# stm32_tracker34.net
KiCad netlist of a schematic drawn in EAGLE
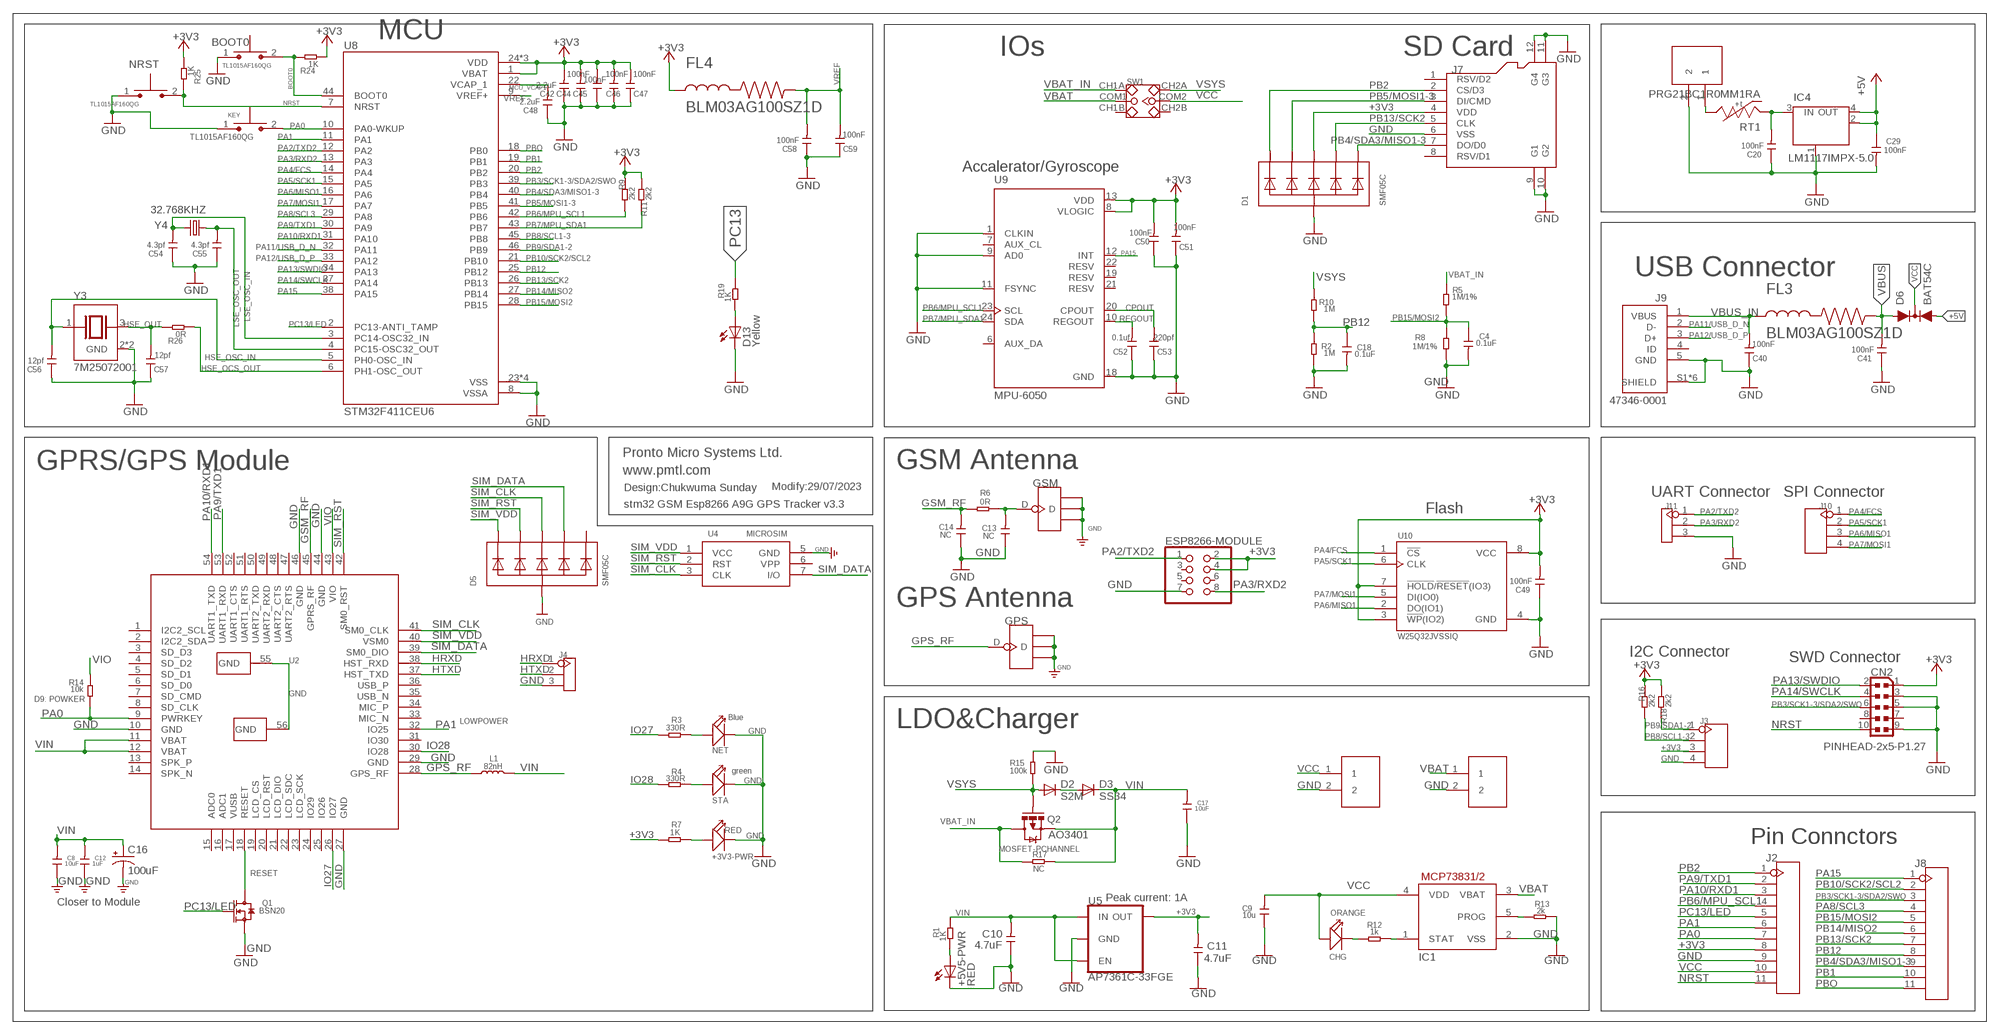
[diagram p0: schematic, sheet 1]

(export (version "E")
  (design (tool "Eeschema 10.0.6"))
  (components
    (comp (ref "+3V3-PWR")
      (value "RED")
      (footprint "eagle-import:LED-0603")
      (libsource (lib "eagle-import") (part "LED'0603'"))
    )
    (comp (ref "+5V5-PWR")
      (value "RED")
      (footprint "eagle-import:OPTO_CHIPLED_0805")
      (fields (field (name "PART_NUMBER") "KPT-2012SGC"))
      (libsource (lib "eagle-import") (part "OPTO_0043_KPT-2012SGC"))
    )
    (comp (ref "BOOT0")
      (value "TL1015AF160QG")
      (footprint "eagle-import:SW_TL1015AF160QG")
      (fields (field (name "MF") "E-Switch"))
      (libsource (lib "eagle-import") (part "TL1015AF160QG"))
    )
    (comp (ref "C4")
      (value "0.1uF")
      (footprint "eagle-import:C0603")
      (libsource (lib "eagle-import") (part "C-0603"))
    )
    (comp (ref "C8")
      (value "10uF")
      (footprint "eagle-import:C0603")
      (libsource (lib "eagle-import") (part "C-0603"))
    )
    (comp (ref "C9")
      (value "10u")
      (footprint "eagle-import:C0603")
      (libsource (lib "eagle-import") (part "C-0603"))
    )
    (comp (ref "C10")
      (value "4.7uF")
      (footprint "eagle-import:C0603")
      (libsource (lib "eagle-import") (part "C-0603"))
    )
    (comp (ref "C11")
      (value "4.7uF")
      (footprint "eagle-import:C0603")
      (libsource (lib "eagle-import") (part "C-0603"))
    )
    (comp (ref "C12")
      (value "1uF")
      (footprint "eagle-import:C0603")
      (libsource (lib "eagle-import") (part "C-0603"))
    )
    (comp (ref "C13")
      (value "NC")
      (footprint "eagle-import:C0402")
      (libsource (lib "eagle-import") (part "C-0402"))
    )
    (comp (ref "C14")
      (value "NC")
      (footprint "eagle-import:C0402")
      (libsource (lib "eagle-import") (part "C-0402"))
    )
    (comp (ref "C16")
      (value "100uF")
      (footprint "eagle-import:EIA3528")
      (libsource (lib "eagle-import") (part "68UF-POLAR-EIA3528-10V-10%(TANT)"))
    )
    (comp (ref "C17")
      (value "10uF")
      (footprint "eagle-import:C0603")
      (libsource (lib "eagle-import") (part "C-0603"))
    )
    (comp (ref "C18")
      (value "0.1uF")
      (footprint "eagle-import:C0603")
      (libsource (lib "eagle-import") (part "C-0603"))
    )
    (comp (ref "C20")
      (value "100nF")
      (footprint "eagle-import:C0603")
      (libsource (lib "eagle-import") (part "C-0603"))
    )
    (comp (ref "C29")
      (value "100nF")
      (footprint "eagle-import:C0603")
      (libsource (lib "eagle-import") (part "C-0603"))
    )
    (comp (ref "C40")
      (value "100nF")
      (footprint "eagle-import:C0603")
      (libsource (lib "eagle-import") (part "C-0603"))
    )
    (comp (ref "C41")
      (value "100nF")
      (footprint "eagle-import:C0603")
      (libsource (lib "eagle-import") (part "C-0603"))
    )
    (comp (ref "C42")
      (value "2.2uF")
      (footprint "eagle-import:C0603")
      (libsource (lib "eagle-import") (part "C-0603"))
    )
    (comp (ref "C44")
      (value "100nF")
      (footprint "eagle-import:C0603")
      (libsource (lib "eagle-import") (part "C-0603"))
    )
    (comp (ref "C45")
      (value "100nF")
      (footprint "eagle-import:C0603")
      (libsource (lib "eagle-import") (part "C-0603"))
    )
    (comp (ref "C46")
      (value "100nF")
      (footprint "eagle-import:C0603")
      (libsource (lib "eagle-import") (part "C-0603"))
    )
    (comp (ref "C47")
      (value "100nF")
      (footprint "eagle-import:C0603")
      (libsource (lib "eagle-import") (part "C-0603"))
    )
    (comp (ref "C48")
      (value "2.2uF")
      (footprint "eagle-import:C0603")
      (libsource (lib "eagle-import") (part "C-0603"))
    )
    (comp (ref "C49")
      (value "100nF")
      (footprint "eagle-import:C0603")
      (libsource (lib "eagle-import") (part "C-0603"))
    )
    (comp (ref "C50")
      (value "100nF")
      (footprint "eagle-import:C0603")
      (libsource (lib "eagle-import") (part "C-0603"))
    )
    (comp (ref "C51")
      (value "100nF")
      (footprint "eagle-import:C0603")
      (libsource (lib "eagle-import") (part "C-0603"))
    )
    (comp (ref "C52")
      (value "0.1uf")
      (footprint "eagle-import:C0603")
      (libsource (lib "eagle-import") (part "C-0603"))
    )
    (comp (ref "C53")
      (value "220pf")
      (footprint "eagle-import:C0603")
      (libsource (lib "eagle-import") (part "C-0603"))
    )
    (comp (ref "C54")
      (value "4.3pf")
      (footprint "eagle-import:C0603")
      (libsource (lib "eagle-import") (part "C-0603"))
    )
    (comp (ref "C55")
      (value "4.3pf")
      (footprint "eagle-import:C0603")
      (libsource (lib "eagle-import") (part "C-0603"))
    )
    (comp (ref "C56")
      (value "12pf")
      (footprint "eagle-import:C0603")
      (libsource (lib "eagle-import") (part "C-0603"))
    )
    (comp (ref "C57")
      (value "12pf")
      (footprint "eagle-import:C0603")
      (libsource (lib "eagle-import") (part "C-0603"))
    )
    (comp (ref "C58")
      (value "100nF")
      (footprint "eagle-import:C0603")
      (libsource (lib "eagle-import") (part "C-0603"))
    )
    (comp (ref "C59")
      (value "100nF")
      (footprint "eagle-import:C0603")
      (libsource (lib "eagle-import") (part "C-0603"))
    )
    (comp (ref "CHG")
      (value "ORANGE")
      (footprint "eagle-import:D0603")
      (libsource (lib "eagle-import") (part "007-LED0603"))
    )
    (comp (ref "CN2")
      (value "PINHEAD-2x5-P1.27")
      (footprint "eagle-import:PINHEAD_2X05_127")
      (libsource (lib "eagle-import") (part "0171_PH127-205DF055G00AROUND-PADS"))
    )
    (comp (ref "D1")
      (value "SMF05C")
      (footprint "eagle-import:SOT363")
      (libsource (lib "eagle-import") (part "TVSARRAY_5LANE"))
    )
    (comp (ref "D2")
      (value "S2M")
      (footprint "eagle-import:DO-214AC")
      (libsource (lib "eagle-import") (part "DIODE-DO-214AC"))
    )
    (comp (ref "D3")
      (value "SS34")
      (footprint "eagle-import:DO-214AC")
      (libsource (lib "eagle-import") (part "DIODE-DO-214AC"))
    )
    (comp (ref "D5")
      (value "SMF05C")
      (footprint "eagle-import:SOT363")
      (libsource (lib "eagle-import") (part "TVSARRAY_5LANE"))
    )
    (comp (ref "D6")
      (value "BAT54C")
      (footprint "eagle-import:SOT23-R")
      (fields (field (name "MF") "Diotec Semiconductor"))
      (libsource (lib "eagle-import") (part "BAT54C"))
    )
    (comp (ref "D13")
      (value "Yellow")
      (footprint "eagle-import:OPTO_CHIPLED_0805")
      (fields (field (name "PART_NUMBER") "KPT-2012YC"))
      (libsource (lib "eagle-import") (part "OPTO_0044_KPT-2012YC"))
    )
    (comp (ref "ESP8266-MODULE")
      (value "PINHD-2X4")
      (footprint "eagle-import:2X04")
      (libsource (lib "eagle-import") (part "PINHD-2X4"))
    )
    (comp (ref "FL3")
      (value "BLM03AG100SZ1D")
      (footprint "eagle-import:BEADC0603X33N")
      (fields (field (name "MF") "Murata"))
      (libsource (lib "eagle-import") (part "BLM03AG100SZ1D"))
    )
    (comp (ref "FL4")
      (value "BLM03AG100SZ1D")
      (footprint "eagle-import:BEADC0603X33N")
      (fields (field (name "MF") "Murata"))
      (libsource (lib "eagle-import") (part "BLM03AG100SZ1D"))
    )
    (comp (ref "GPS")
      (value "ANTENNA-U-FL")
      (footprint "eagle-import:4P-U-FL")
      (libsource (lib "eagle-import") (part "ANTENNA-U-FL"))
    )
    (comp (ref "GSM")
      (value "ANTENNA-U-FL")
      (footprint "eagle-import:4P-U-FL")
      (libsource (lib "eagle-import") (part "ANTENNA-U-FL"))
    )
    (comp (ref "IC1")
      (value "MCP73831/OT")
      (footprint "eagle-import:SOT23-5L")
      (libsource (lib "eagle-import") (part "MCP73831/OT"))
    )
    (comp (ref "IC4")
      (value "LM1117IMPX-5.0")
      (footprint "eagle-import:INTEGRATEDCIRCUITS_LINEAR_SOT223")
      (libsource (lib "eagle-import") (part "INTEGRATEDCIRCUITS_0022_LM1117IMPX-5.0"))
    )
    (comp (ref "J1")
      (value "PH2.0-2P-90-DIP")
      (footprint "eagle-import:PH2.0-2P-90-DIP")
      (libsource (lib "eagle-import") (part "PH2.0-2P-90-DIP"))
    )
    (comp (ref "J2")
      (value "HEADER-11P-2.54")
      (footprint "eagle-import:11P-2.54")
      (libsource (lib "eagle-import") (part "HEADER-11P-2.54"))
    )
    (comp (ref "J3")
      (value "HEADER-4P-60/35MILROUND")
      (footprint "eagle-import:4P-65_35ROUND")
      (libsource (lib "eagle-import") (part "HEADER-4P-60/35MILROUND"))
    )
    (comp (ref "J4")
      (value "HEADER-3P-2.54")
      (footprint "eagle-import:3P-2.54")
      (libsource (lib "eagle-import") (part "HEADER-3P-2.54"))
    )
    (comp (ref "J5")
      (value "PH2.0-2P-90-DIP")
      (footprint "eagle-import:PH2.0-2P-90-DIP")
      (libsource (lib "eagle-import") (part "PH2.0-2P-90-DIP"))
    )
    (comp (ref "J6")
      (value "PH2.0-2P-90-DIP")
      (footprint "eagle-import:PH2.0-2P-90-DIP")
      (libsource (lib "eagle-import") (part "PH2.0-2P-90-DIP"))
    )
    (comp (ref "J7")
      (value "HOLDER-MICROSD-8P")
      (footprint "eagle-import:8P-SMD")
      (libsource (lib "eagle-import") (part "HOLDER-MICROSD-8P"))
    )
    (comp (ref "J8")
      (value "HEADER-11P-2.54")
      (footprint "eagle-import:11P-2.54")
      (libsource (lib "eagle-import") (part "HEADER-11P-2.54"))
    )
    (comp (ref "J9")
      (value "47346-0001")
      (footprint "eagle-import:MOLEX_47346-0001")
      (fields (field (name "MF") "Molex"))
      (libsource (lib "eagle-import") (part "47346-0001"))
    )
    (comp (ref "J10")
      (value "HEADER-4P-60/35MILROUND")
      (footprint "eagle-import:4P-65_35ROUND")
      (libsource (lib "eagle-import") (part "HEADER-4P-60/35MILROUND"))
    )
    (comp (ref "J11")
      (value "HEADER-3P-2.54")
      (footprint "eagle-import:3P-2.54")
      (libsource (lib "eagle-import") (part "HEADER-3P-2.54"))
    )
    (comp (ref "KEY")
      (value "TL1015AF160QG")
      (footprint "eagle-import:SW_TL1015AF160QG")
      (fields (field (name "MF") "E-Switch"))
      (libsource (lib "eagle-import") (part "TL1015AF160QG"))
    )
    (comp (ref "L1")
      (value "82nH")
      (footprint "eagle-import:L0603")
      (libsource (lib "eagle-import") (part "L'0603'"))
    )
    (comp (ref "NET")
      (value "Blue")
      (footprint "eagle-import:LED-0603")
      (libsource (lib "eagle-import") (part "LED'0603'"))
    )
    (comp (ref "NRST")
      (value "TL1015AF160QG")
      (footprint "eagle-import:SW_TL1015AF160QG")
      (fields (field (name "MF") "E-Switch"))
      (libsource (lib "eagle-import") (part "TL1015AF160QG"))
    )
    (comp (ref "Q1")
      (value "BSN20")
      (footprint "eagle-import:SOT23@1")
      (libsource (lib "eagle-import") (part "MOSFET-N'SOT23'"))
    )
    (comp (ref "Q2")
      (value "MOSFET-PCHANNEL")
      (footprint "eagle-import:SOT23-3")
      (libsource (lib "eagle-import") (part "MOSFET-PCHANNEL"))
    )
    (comp (ref "R1")
      (value "1K")
      (footprint "eagle-import:R0603")
      (libsource (lib "eagle-import") (part "R-0603"))
    )
    (comp (ref "R2")
      (value "1M")
      (footprint "eagle-import:R0603")
      (libsource (lib "eagle-import") (part "R-0603"))
    )
    (comp (ref "R3")
      (value "330R")
      (footprint "eagle-import:R0603")
      (libsource (lib "eagle-import") (part "R-0603"))
    )
    (comp (ref "R4")
      (value "330R")
      (footprint "eagle-import:R0603")
      (libsource (lib "eagle-import") (part "R-0603"))
    )
    (comp (ref "R5")
      (value "1M/1%")
      (footprint "eagle-import:R0603")
      (libsource (lib "eagle-import") (part "R-0603"))
    )
    (comp (ref "R6")
      (value "0R")
      (footprint "eagle-import:R0603")
      (libsource (lib "eagle-import") (part "R-0603"))
    )
    (comp (ref "R7")
      (value "1K")
      (footprint "eagle-import:R0603")
      (libsource (lib "eagle-import") (part "R-0603"))
    )
    (comp (ref "R8")
      (value "1M/1%")
      (footprint "eagle-import:R0603")
      (libsource (lib "eagle-import") (part "R-0603"))
    )
    (comp (ref "R9")
      (value "2k2")
      (footprint "eagle-import:R0603")
      (libsource (lib "eagle-import") (part "R-0603"))
    )
    (comp (ref "R10")
      (value "1M")
      (footprint "eagle-import:R0603")
      (libsource (lib "eagle-import") (part "R-0603"))
    )
    (comp (ref "R11")
      (value "2k2")
      (footprint "eagle-import:R0603")
      (libsource (lib "eagle-import") (part "R-0603"))
    )
    (comp (ref "R12")
      (value "1k")
      (footprint "eagle-import:R0603")
      (libsource (lib "eagle-import") (part "R-0603"))
    )
    (comp (ref "R13")
      (value "2k")
      (footprint "eagle-import:R0603")
      (libsource (lib "eagle-import") (part "R-0603"))
    )
    (comp (ref "R14")
      (value "10k")
      (footprint "eagle-import:R0603")
      (libsource (lib "eagle-import") (part "R-0603"))
    )
    (comp (ref "R15")
      (value "100k")
      (footprint "eagle-import:R0603")
      (libsource (lib "eagle-import") (part "R-0603"))
    )
    (comp (ref "R16")
      (value "2k2")
      (footprint "eagle-import:R0603")
      (libsource (lib "eagle-import") (part "R-0603"))
    )
    (comp (ref "R17")
      (value "NC")
      (footprint "eagle-import:R0603")
      (libsource (lib "eagle-import") (part "R-0603"))
    )
    (comp (ref "R18")
      (value "2k2")
      (footprint "eagle-import:R0603")
      (libsource (lib "eagle-import") (part "R-0603"))
    )
    (comp (ref "R19")
      (value "1K")
      (footprint "eagle-import:R0603")
      (libsource (lib "eagle-import") (part "R-0603"))
    )
    (comp (ref "R24")
      (value "1K")
      (footprint "eagle-import:R0603")
      (libsource (lib "eagle-import") (part "R-0603"))
    )
    (comp (ref "R25")
      (value "1K")
      (footprint "eagle-import:R0603")
      (libsource (lib "eagle-import") (part "R-0603"))
    )
    (comp (ref "R26")
      (value "0R")
      (footprint "eagle-import:R0603")
      (libsource (lib "eagle-import") (part "R-0603"))
    )
    (comp (ref "RT1")
      (value "PRG21BC1R0MM1RA")
      (footprint "eagle-import:THRMC2012X110N")
      (fields (field (name "MF") "Murata"))
      (libsource (lib "eagle-import") (part "PRG21BC1R0MM1RA"))
    )
    (comp (ref "STA")
      (value "green")
      (footprint "eagle-import:LED-0603")
      (libsource (lib "eagle-import") (part "LED'0603'"))
    )
    (comp (ref "SW1")
      (value "SWITCH-2CH-6P")
      (footprint "eagle-import:6P-2CH-2.54-7.6X3.0")
      (libsource (lib "eagle-import") (part "SWITCH-2CH-6P"))
    )
    (comp (ref "U2")
      (value "A9G")
      (footprint "eagle-import:A9G")
      (libsource (lib "eagle-import") (part "A9G"))
    )
    (comp (ref "U4")
      (value "MICROSIM")
      (footprint "eagle-import:MICROSIM")
      (libsource (lib "eagle-import") (part "MICROSIM"))
    )
    (comp (ref "U5")
      (value "AP7361C-33FGE")
      (footprint "eagle-import:8-UDFN")
      (libsource (lib "eagle-import") (part "AP7361C-33FGE"))
    )
    (comp (ref "U8")
      (value "STM32F411CEU6")
      (footprint "eagle-import:QFN50P700X700X60-49N")
      (fields (field (name "MF") "STMicroelectronics"))
      (libsource (lib "eagle-import") (part "STM32F411CEU6"))
    )
    (comp (ref "U9")
      (value "MPU-6050")
      (footprint "eagle-import:QFN50P400X400X95-24N")
      (fields (field (name "MF") "TDK InvenSense"))
      (libsource (lib "eagle-import") (part "MPU-6050"))
    )
    (comp (ref "U10")
      (value "W25Q32JVSSIQ")
      (footprint "eagle-import:SOIC127P790X216-8N")
      (fields (field (name "MF") "Winbond"))
      (libsource (lib "eagle-import") (part "W25Q32JVSSIQ"))
    )
    (comp (ref "Y3")
      (value "7M25072001")
      (footprint "eagle-import:XTAL_7M25072001")
      (fields (field (name "MF") "TXC"))
      (libsource (lib "eagle-import") (part "7M25072001"))
    )
    (comp (ref "Y4")
      (value "32.768KHZ")
      (footprint "eagle-import:XTAL160X100X50")
      (fields (field (name "MF") "TXC") (field (name "MP") "9HT12-32.768KDZF-T"))
      (libsource (lib "eagle-import") (part "9HT12-32.768KDZF-T"))
    )
  )
  (nets
    (net (code "1") (name "+3V3") (class "Default")
      (node (ref "C11") (pin "2") (pinfunction "2_2") (pintype "passive"))
      (node (ref "C42") (pin "2") (pinfunction "2_2") (pintype "passive"))
      (node (ref "C44") (pin "2") (pinfunction "2_2") (pintype "passive"))
      (node (ref "C45") (pin "2") (pinfunction "2_2") (pintype "passive"))
      (node (ref "C46") (pin "2") (pinfunction "2_2") (pintype "passive"))
      (node (ref "C47") (pin "2") (pinfunction "2_2") (pintype "passive"))
      (node (ref "C49") (pin "2") (pinfunction "2_2") (pintype "passive"))
      (node (ref "C50") (pin "2") (pinfunction "2_2") (pintype "passive"))
      (node (ref "C51") (pin "2") (pinfunction "2_2") (pintype "passive"))
      (node (ref "CN2") (pin "1") (pinfunction "1_1") (pintype "passive"))
      (node (ref "D1") (pin "4") (pinfunction "C3_4") (pintype "passive"))
      (node (ref "ESP8266-MODULE") (pin "2") (pinfunction "2_2") (pintype "passive"))
      (node (ref "ESP8266-MODULE") (pin "4") (pinfunction "4_4") (pintype "passive"))
      (node (ref "FL4") (pin "1") (pinfunction "1_1") (pintype "passive"))
      (node (ref "J2") (pin "8") (pinfunction "8_8") (pintype "bidirectional"))
      (node (ref "J3") (pin "3") (pinfunction "P$3_3") (pintype "bidirectional"))
      (node (ref "J7") (pin "4") (pinfunction "VDD_4") (pintype "bidirectional"))
      (node (ref "R11") (pin "1") (pinfunction "1_1") (pintype "passive"))
      (node (ref "R16") (pin "1") (pinfunction "1_1") (pintype "passive"))
      (node (ref "R18") (pin "1") (pinfunction "1_1") (pintype "passive"))
      (node (ref "R24") (pin "1") (pinfunction "1_1") (pintype "passive"))
      (node (ref "R25") (pin "1") (pinfunction "1_1") (pintype "passive"))
      (node (ref "R7") (pin "1") (pinfunction "1_1") (pintype "passive"))
      (node (ref "R9") (pin "1") (pinfunction "1_1") (pintype "passive"))
      (node (ref "U10") (pin "3") (pinfunction "~{WP}(IO2)_3") (pintype "bidirectional"))
      (node (ref "U10") (pin "7") (pinfunction "~{HOLD}/~{RESET}(IO3)_7") (pintype "bidirectional"))
      (node (ref "U10") (pin "8") (pinfunction "VCC_8") (pintype "power_in"))
      (node (ref "U5") (pin "1") (pinfunction "OUT_1") (pintype "output"))
      (node (ref "U8") (pin "1") (pinfunction "VBAT_1") (pintype "power_in"))
      (node (ref "U8") (pin "24") (pinfunction "VDD_24") (pintype "power_in"))
      (node (ref "U8") (pin "36") (pinfunction "VDD_36") (pintype "power_in"))
      (node (ref "U8") (pin "48") (pinfunction "VDD_48") (pintype "power_in"))
      (node (ref "U9") (pin "13") (pinfunction "VDD_13") (pintype "power_in"))
      (node (ref "U9") (pin "8") (pinfunction "VLOGIC_8") (pintype "power_in"))
    )
    (net (code "2") (name "+5V") (class "Default")
      (node (ref "C29") (pin "1") (pinfunction "1_1") (pintype "passive"))
      (node (ref "D6") (pin "2") (pinfunction "A2_2") (pintype "passive"))
      (node (ref "IC4") (pin "2") (pinfunction "OUT_2") (pintype "passive"))
      (node (ref "IC4") (pin "4") (pinfunction "OUT_4") (pintype "passive"))
    )
    (net (code "3") (name "/BOOT0") (class "Default")
      (node (ref "BOOT0") (pin "2") (pinfunction "2_2") (pintype "passive"))
      (node (ref "R24") (pin "2") (pinfunction "2_2") (pintype "passive"))
      (node (ref "U8") (pin "44") (pinfunction "BOOT0_44") (pintype "input"))
    )
    (net (code "4") (name "/CPOUT") (class "Default")
      (node (ref "C53") (pin "2") (pinfunction "2_2") (pintype "passive"))
      (node (ref "U9") (pin "20") (pinfunction "CPOUT_20") (pintype "passive"))
    )
    (net (code "5") (name "/GPS_RF") (class "Default")
      (node (ref "GPS") (pin "D") (pinfunction "D_D") (pintype "bidirectional"))
      (node (ref "L1") (pin "1") (pinfunction "1_1") (pintype "passive"))
      (node (ref "U2") (pin "28") (pinfunction "GPS_RF_28") (pintype "bidirectional"))
    )
    (net (code "6") (name "/GSM_RF") (class "Default")
      (node (ref "C14") (pin "2") (pinfunction "2_2") (pintype "passive"))
      (node (ref "R6") (pin "1") (pinfunction "1_1") (pintype "passive"))
      (node (ref "U2") (pin "45") (pinfunction "GPRS_RF_45") (pintype "bidirectional"))
    )
    (net (code "7") (name "/HRXD") (class "Default")
      (node (ref "J4") (pin "1") (pinfunction "P$1_1") (pintype "bidirectional"))
      (node (ref "U2") (pin "38") (pinfunction "HST_RXD_38") (pintype "bidirectional"))
    )
    (net (code "8") (name "/HSE_OCS_OUT") (class "Default")
      (node (ref "R26") (pin "1") (pinfunction "1_1") (pintype "passive"))
      (node (ref "U8") (pin "6") (pinfunction "PH1-OSC_OUT_6") (pintype "bidirectional"))
    )
    (net (code "9") (name "/HSE_OSC_IN") (class "Default")
      (node (ref "C56") (pin "2") (pinfunction "2_2") (pintype "passive"))
      (node (ref "U8") (pin "5") (pinfunction "PH0-OSC_IN_5") (pintype "bidirectional"))
      (node (ref "Y3") (pin "1") (pinfunction "1_1") (pintype "passive"))
    )
    (net (code "10") (name "/HSE_OUT") (class "Default")
      (node (ref "C57") (pin "2") (pinfunction "2_2") (pintype "passive"))
      (node (ref "R26") (pin "2") (pinfunction "2_2") (pintype "passive"))
      (node (ref "Y3") (pin "3") (pinfunction "2_3") (pintype "passive"))
    )
    (net (code "11") (name "/HTXD") (class "Default")
      (node (ref "J4") (pin "2") (pinfunction "P$2_2") (pintype "bidirectional"))
      (node (ref "U2") (pin "37") (pinfunction "HST_TXD_37") (pintype "bidirectional"))
    )
    (net (code "12") (name "/IO27") (class "Default")
      (node (ref "R3") (pin "1") (pinfunction "1_1") (pintype "passive"))
      (node (ref "U2") (pin "26") (pinfunction "IO27_26") (pintype "bidirectional"))
    )
    (net (code "13") (name "/IO28") (class "Default")
      (node (ref "R4") (pin "1") (pinfunction "1_1") (pintype "passive"))
      (node (ref "U2") (pin "30") (pinfunction "IO28_30") (pintype "bidirectional"))
    )
    (net (code "14") (name "/LSE_OSC_IN") (class "Default")
      (node (ref "C54") (pin "2") (pinfunction "2_2") (pintype "passive"))
      (node (ref "U8") (pin "3") (pinfunction "PC14-OSC32_IN_3") (pintype "bidirectional"))
      (node (ref "Y4") (pin "2") (pinfunction "2_2") (pintype "passive"))
    )
    (net (code "15") (name "/LSE_OSC_OUT") (class "Default")
      (node (ref "C55") (pin "2") (pinfunction "2_2") (pintype "passive"))
      (node (ref "U8") (pin "4") (pinfunction "PC15-OSC32_OUT_4") (pintype "bidirectional"))
      (node (ref "Y4") (pin "1") (pinfunction "1_1") (pintype "passive"))
    )
    (net (code "16") (name "/MCU_VCAP1") (class "Default")
      (node (ref "C48") (pin "2") (pinfunction "2_2") (pintype "passive"))
      (node (ref "U8") (pin "22") (pinfunction "VCAP_1_22") (pintype "power_in"))
    )
    (net (code "17") (name "/NRST") (class "Default")
      (node (ref "CN2") (pin "10") (pinfunction "10_10") (pintype "passive"))
      (node (ref "J2") (pin "11") (pinfunction "11_11") (pintype "bidirectional"))
      (node (ref "NRST") (pin "2") (pinfunction "2_2") (pintype "passive"))
      (node (ref "R25") (pin "2") (pinfunction "2_2") (pintype "passive"))
      (node (ref "U8") (pin "7") (pinfunction "NRST_7") (pintype "bidirectional"))
    )
    (net (code "18") (name "/PA0") (class "Default")
      (node (ref "J2") (pin "7") (pinfunction "7_7") (pintype "bidirectional"))
      (node (ref "KEY") (pin "2") (pinfunction "2_2") (pintype "passive"))
      (node (ref "R14") (pin "1") (pinfunction "1_1") (pintype "passive"))
      (node (ref "U2") (pin "9") (pinfunction "PWRKEY_9") (pintype "bidirectional"))
      (node (ref "U8") (pin "10") (pinfunction "PA0-WKUP_10") (pintype "bidirectional"))
    )
    (net (code "19") (name "/PA1") (class "Default")
      (node (ref "J2") (pin "6") (pinfunction "6_6") (pintype "bidirectional"))
      (node (ref "U2") (pin "32") (pinfunction "IO25_32") (pintype "bidirectional"))
      (node (ref "U8") (pin "11") (pinfunction "PA1_11") (pintype "bidirectional"))
    )
    (net (code "20") (name "/PA2{slash}TXD2") (class "Default")
      (node (ref "ESP8266-MODULE") (pin "1") (pinfunction "1_1") (pintype "passive"))
      (node (ref "J11") (pin "1") (pinfunction "P$1_1") (pintype "bidirectional"))
      (node (ref "U8") (pin "12") (pinfunction "PA2_12") (pintype "bidirectional"))
    )
    (net (code "21") (name "/PA3{slash}RXD2") (class "Default")
      (node (ref "ESP8266-MODULE") (pin "8") (pinfunction "8_8") (pintype "passive"))
      (node (ref "J11") (pin "2") (pinfunction "P$2_2") (pintype "bidirectional"))
      (node (ref "U8") (pin "13") (pinfunction "PA3_13") (pintype "bidirectional"))
    )
    (net (code "22") (name "/PA4{slash}FCS") (class "Default")
      (node (ref "J10") (pin "1") (pinfunction "P$1_1") (pintype "bidirectional"))
      (node (ref "U10") (pin "1") (pinfunction "~{CS}_1") (pintype "input"))
      (node (ref "U8") (pin "14") (pinfunction "PA4_14") (pintype "bidirectional"))
    )
    (net (code "23") (name "/PA5{slash}SCK1") (class "Default")
      (node (ref "J10") (pin "2") (pinfunction "P$2_2") (pintype "bidirectional"))
      (node (ref "U10") (pin "6") (pinfunction "CLK_6") (pintype "input"))
      (node (ref "U8") (pin "15") (pinfunction "PA5_15") (pintype "bidirectional"))
    )
    (net (code "24") (name "/PA6{slash}MISO1") (class "Default")
      (node (ref "J10") (pin "3") (pinfunction "P$3_3") (pintype "bidirectional"))
      (node (ref "U10") (pin "2") (pinfunction "DO(IO1)_2") (pintype "bidirectional"))
      (node (ref "U8") (pin "16") (pinfunction "PA6_16") (pintype "bidirectional"))
    )
    (net (code "25") (name "/PA7{slash}MOSI1") (class "Default")
      (node (ref "J10") (pin "4") (pinfunction "P$4_4") (pintype "bidirectional"))
      (node (ref "U10") (pin "5") (pinfunction "DI(IO0)_5") (pintype "bidirectional"))
      (node (ref "U8") (pin "17") (pinfunction "PA7_17") (pintype "bidirectional"))
    )
    (net (code "26") (name "/PA8{slash}SCL3") (class "Default")
      (node (ref "J8") (pin "4") (pinfunction "4_4") (pintype "bidirectional"))
      (node (ref "U8") (pin "29") (pinfunction "PA8_29") (pintype "bidirectional"))
    )
    (net (code "27") (name "/PA9{slash}TXD1") (class "Default")
      (node (ref "J2") (pin "2") (pinfunction "2_2") (pintype "bidirectional"))
      (node (ref "U2") (pin "53") (pinfunction "UART1_RXD_53") (pintype "bidirectional"))
      (node (ref "U8") (pin "30") (pinfunction "PA9_30") (pintype "bidirectional"))
    )
    (net (code "28") (name "/PA10{slash}RXD1") (class "Default")
      (node (ref "J2") (pin "3") (pinfunction "3_3") (pintype "bidirectional"))
      (node (ref "U2") (pin "54") (pinfunction "UART1_TXD_54") (pintype "bidirectional"))
      (node (ref "U8") (pin "31") (pinfunction "PA10_31") (pintype "bidirectional"))
    )
    (net (code "29") (name "/PA11{slash}USB_D_N") (class "Default")
      (node (ref "J9") (pin "2") (pinfunction "D-_2") (pintype "bidirectional"))
      (node (ref "U8") (pin "32") (pinfunction "PA11_32") (pintype "bidirectional"))
    )
    (net (code "30") (name "/PA12{slash}USB_D_P") (class "Default")
      (node (ref "J9") (pin "3") (pinfunction "D+_3") (pintype "bidirectional"))
      (node (ref "U8") (pin "33") (pinfunction "PA12_33") (pintype "bidirectional"))
    )
    (net (code "31") (name "/PA13{slash}SWDIO") (class "Default")
      (node (ref "CN2") (pin "2") (pinfunction "2_2") (pintype "passive"))
      (node (ref "U8") (pin "34") (pinfunction "PA13_34") (pintype "bidirectional"))
    )
    (net (code "32") (name "/PA14{slash}SWCLK") (class "Default")
      (node (ref "CN2") (pin "4") (pinfunction "4_4") (pintype "passive"))
      (node (ref "U8") (pin "37") (pinfunction "PA14_37") (pintype "bidirectional"))
    )
    (net (code "33") (name "/PA15") (class "Default")
      (node (ref "J8") (pin "1") (pinfunction "1_1") (pintype "bidirectional"))
      (node (ref "U8") (pin "38") (pinfunction "PA15_38") (pintype "bidirectional"))
      (node (ref "U9") (pin "12") (pinfunction "INT_12") (pintype "output"))
    )
    (net (code "34") (name "/PB1") (class "Default")
      (node (ref "J8") (pin "10") (pinfunction "10_10") (pintype "bidirectional"))
      (node (ref "U8") (pin "19") (pinfunction "PB1_19") (pintype "bidirectional"))
    )
    (net (code "35") (name "/PB2") (class "Default")
      (node (ref "D1") (pin "1") (pinfunction "C1_1") (pintype "passive"))
      (node (ref "J2") (pin "1") (pinfunction "1_1") (pintype "bidirectional"))
      (node (ref "J7") (pin "2") (pinfunction "CS/D3_2") (pintype "bidirectional"))
      (node (ref "U8") (pin "20") (pinfunction "PB2_20") (pintype "bidirectional"))
    )
    (net (code "36") (name "/PB3{slash}SCK1-3{slash}SDA2{slash}SWO") (class "Default")
      (node (ref "CN2") (pin "6") (pinfunction "6_6") (pintype "passive"))
      (node (ref "J8") (pin "3") (pinfunction "3_3") (pintype "bidirectional"))
      (node (ref "U8") (pin "39") (pinfunction "PB3_39") (pintype "bidirectional"))
    )
    (net (code "37") (name "/PB4{slash}SDA3{slash}MISO1-3") (class "Default")
      (node (ref "D1") (pin "6") (pinfunction "C5_6") (pintype "passive"))
      (node (ref "J7") (pin "7") (pinfunction "DO/D0_7") (pintype "bidirectional"))
      (node (ref "J8") (pin "9") (pinfunction "9_9") (pintype "bidirectional"))
      (node (ref "U8") (pin "40") (pinfunction "PB4_40") (pintype "bidirectional"))
    )
    (net (code "38") (name "/PB5{slash}MOSI1-3") (class "Default")
      (node (ref "D1") (pin "3") (pinfunction "C2_3") (pintype "passive"))
      (node (ref "J7") (pin "3") (pinfunction "DI/CMD_3") (pintype "bidirectional"))
      (node (ref "U8") (pin "41") (pinfunction "PB5_41") (pintype "bidirectional"))
    )
    (net (code "39") (name "/PB6{slash}MPU_SCL1") (class "Default")
      (node (ref "J2") (pin "4") (pinfunction "4_4") (pintype "bidirectional"))
      (node (ref "R9") (pin "2") (pinfunction "2_2") (pintype "passive"))
      (node (ref "U8") (pin "42") (pinfunction "PB6_42") (pintype "bidirectional"))
      (node (ref "U9") (pin "23") (pinfunction "SCL_23") (pintype "input"))
    )
    (net (code "40") (name "/PB7{slash}MPU_SDA1") (class "Default")
      (node (ref "R11") (pin "2") (pinfunction "2_2") (pintype "passive"))
      (node (ref "U8") (pin "43") (pinfunction "PB7_43") (pintype "bidirectional"))
      (node (ref "U9") (pin "24") (pinfunction "SDA_24") (pintype "bidirectional"))
    )
    (net (code "41") (name "/PB8{slash}SCL1-3") (class "Default")
      (node (ref "J3") (pin "2") (pinfunction "P$2_2") (pintype "bidirectional"))
      (node (ref "R16") (pin "2") (pinfunction "2_2") (pintype "passive"))
      (node (ref "U8") (pin "45") (pinfunction "PB8_45") (pintype "bidirectional"))
    )
    (net (code "42") (name "/PB9{slash}SDA1-2") (class "Default")
      (node (ref "J3") (pin "1") (pinfunction "P$1_1") (pintype "bidirectional"))
      (node (ref "R18") (pin "2") (pinfunction "2_2") (pintype "passive"))
      (node (ref "U8") (pin "46") (pinfunction "PB9_46") (pintype "bidirectional"))
    )
    (net (code "43") (name "/PB10{slash}SCK2{slash}SCL2") (class "Default")
      (node (ref "J8") (pin "2") (pinfunction "2_2") (pintype "bidirectional"))
      (node (ref "U8") (pin "21") (pinfunction "PB10_21") (pintype "bidirectional"))
    )
    (net (code "44") (name "/PB12") (class "Default")
      (node (ref "C18") (pin "1") (pinfunction "1_1") (pintype "passive"))
      (node (ref "J8") (pin "8") (pinfunction "8_8") (pintype "bidirectional"))
      (node (ref "R10") (pin "1") (pinfunction "1_1") (pintype "passive"))
      (node (ref "R2") (pin "2") (pinfunction "2_2") (pintype "passive"))
      (node (ref "U8") (pin "25") (pinfunction "PB12_25") (pintype "bidirectional"))
    )
    (net (code "45") (name "/PB13{slash}SCK2") (class "Default")
      (node (ref "D1") (pin "5") (pinfunction "C4_5") (pintype "passive"))
      (node (ref "J7") (pin "5") (pinfunction "CLK_5") (pintype "bidirectional"))
      (node (ref "J8") (pin "7") (pinfunction "7_7") (pintype "bidirectional"))
      (node (ref "U8") (pin "26") (pinfunction "PB13_26") (pintype "bidirectional"))
    )
    (net (code "46") (name "/PB14{slash}MISO2") (class "Default")
      (node (ref "J8") (pin "6") (pinfunction "6_6") (pintype "bidirectional"))
      (node (ref "U8") (pin "27") (pinfunction "PB14_27") (pintype "bidirectional"))
    )
    (net (code "47") (name "/PB15{slash}MOSI2") (class "Default")
      (node (ref "C4") (pin "1") (pinfunction "1_1") (pintype "passive"))
      (node (ref "J8") (pin "5") (pinfunction "5_5") (pintype "bidirectional"))
      (node (ref "R5") (pin "1") (pinfunction "1_1") (pintype "passive"))
      (node (ref "R8") (pin "2") (pinfunction "2_2") (pintype "passive"))
      (node (ref "U8") (pin "28") (pinfunction "PB15_28") (pintype "bidirectional"))
    )
    (net (code "48") (name "/PBO") (class "Default")
      (node (ref "J8") (pin "11") (pinfunction "11_11") (pintype "bidirectional"))
      (node (ref "U8") (pin "18") (pinfunction "PB0_18") (pintype "bidirectional"))
    )
    (net (code "49") (name "/PC13{slash}LED") (class "Default")
      (node (ref "J2") (pin "5") (pinfunction "5_5") (pintype "bidirectional"))
      (node (ref "Q1") (pin "1") (pinfunction "G_1") (pintype "passive"))
      (node (ref "U8") (pin "2") (pinfunction "PC13-ANTI_TAMP_2") (pintype "bidirectional"))
    )
    (net (code "50") (name "/REGOUT") (class "Default")
      (node (ref "C52") (pin "2") (pinfunction "2_2") (pintype "passive"))
      (node (ref "U9") (pin "10") (pinfunction "REGOUT_10") (pintype "passive"))
    )
    (net (code "51") (name "/SIM_CLK") (class "Default")
      (node (ref "D5") (pin "4") (pinfunction "C3_4") (pintype "passive"))
      (node (ref "U2") (pin "41") (pinfunction "SM0_CLK_41") (pintype "bidirectional"))
      (node (ref "U4") (pin "3") (pinfunction "CLK_3") (pintype "bidirectional"))
    )
    (net (code "52") (name "/SIM_DATA") (class "Default")
      (node (ref "D5") (pin "5") (pinfunction "C4_5") (pintype "passive"))
      (node (ref "U2") (pin "39") (pinfunction "SM0_DIO_39") (pintype "bidirectional"))
      (node (ref "U4") (pin "7") (pinfunction "I/O_7") (pintype "bidirectional"))
    )
    (net (code "53") (name "/SIM_RST") (class "Default")
      (node (ref "D5") (pin "3") (pinfunction "C2_3") (pintype "passive"))
      (node (ref "U2") (pin "42") (pinfunction "SM0_RST_42") (pintype "bidirectional"))
      (node (ref "U4") (pin "2") (pinfunction "RST_2") (pintype "bidirectional"))
    )
    (net (code "54") (name "/SIM_VDD") (class "Default")
      (node (ref "D5") (pin "1") (pinfunction "C1_1") (pintype "passive"))
      (node (ref "U2") (pin "40") (pinfunction "VSM0_40") (pintype "bidirectional"))
      (node (ref "U4") (pin "1") (pinfunction "VCC_1") (pintype "bidirectional"))
    )
    (net (code "55") (name "/VBAT") (class "Default")
      (node (ref "IC1") (pin "3") (pinfunction "VBAT_3") (pintype "bidirectional"))
      (node (ref "J6") (pin "1") (pinfunction "1_1") (pintype "bidirectional"))
      (node (ref "SW1") (pin "COM1") (pinfunction "COM1_COM1") (pintype "bidirectional"))
    )
    (net (code "56") (name "/VBAT_IN") (class "Default")
      (node (ref "Q2") (pin "3") (pinfunction "D_3") (pintype "passive"))
      (node (ref "R17") (pin "1") (pinfunction "1_1") (pintype "passive"))
      (node (ref "R5") (pin "2") (pinfunction "2_2") (pintype "passive"))
      (node (ref "SW1") (pin "CH1A") (pinfunction "CH1A_CH1A") (pintype "bidirectional"))
    )
    (net (code "57") (name "/VBUS_IN") (class "Default")
      (node (ref "C40") (pin "2") (pinfunction "2_2") (pintype "passive"))
      (node (ref "FL3") (pin "1") (pinfunction "1_1") (pintype "passive"))
      (node (ref "J9") (pin "1") (pinfunction "VBUS_1") (pintype "power_in"))
    )
    (net (code "58") (name "/VIN") (class "Default")
      (node (ref "C10") (pin "2") (pinfunction "2_2") (pintype "passive"))
      (node (ref "C12") (pin "2") (pinfunction "2_2") (pintype "passive"))
      (node (ref "C16") (pin "A") (pinfunction "+_A") (pintype "passive"))
      (node (ref "C17") (pin "2") (pinfunction "2_2") (pintype "passive"))
      (node (ref "C8") (pin "2") (pinfunction "2_2") (pintype "passive"))
      (node (ref "D3") (pin "C") (pinfunction "C_C") (pintype "passive"))
      (node (ref "L1") (pin "2") (pinfunction "2_2") (pintype "passive"))
      (node (ref "Q2") (pin "2") (pinfunction "S_2") (pintype "passive"))
      (node (ref "R1") (pin "2") (pinfunction "2_2") (pintype "passive"))
      (node (ref "R17") (pin "2") (pinfunction "2_2") (pintype "passive"))
      (node (ref "U2") (pin "11") (pinfunction "VBAT_11") (pintype "bidirectional"))
      (node (ref "U2") (pin "12") (pinfunction "VBAT_12") (pintype "bidirectional"))
      (node (ref "U5") (pin "5") (pinfunction "EN_5") (pintype "bidirectional"))
      (node (ref "U5") (pin "8") (pinfunction "IN_8") (pintype "input"))
    )
    (net (code "59") (name "/VIO") (class "Default")
      (node (ref "R14") (pin "2") (pinfunction "2_2") (pintype "passive"))
      (node (ref "U2") (pin "43") (pinfunction "VIO_43") (pintype "bidirectional"))
    )
    (net (code "60") (name "/VREF") (class "Default")
      (node (ref "C58") (pin "2") (pinfunction "2_2") (pintype "passive"))
      (node (ref "C59") (pin "2") (pinfunction "2_2") (pintype "passive"))
      (node (ref "FL4") (pin "2") (pinfunction "2_2") (pintype "passive"))
      (node (ref "U8") (pin "9") (pinfunction "VREF+_9") (pintype "power_in"))
    )
    (net (code "61") (name "/VSYS") (class "Default")
      (node (ref "D2") (pin "A") (pinfunction "A_A") (pintype "passive"))
      (node (ref "Q2") (pin "1") (pinfunction "G_1") (pintype "passive"))
      (node (ref "R10") (pin "2") (pinfunction "2_2") (pintype "passive"))
      (node (ref "R15") (pin "1") (pinfunction "1_1") (pintype "passive"))
      (node (ref "SW1") (pin "CH2A") (pinfunction "CH2A_CH2A") (pintype "bidirectional"))
    )
    (net (code "62") (name "GND") (class "Default")
      (node (ref "+3V3-PWR") (pin "-") (pinfunction "-_-") (pintype "passive"))
      (node (ref "+5V5-PWR") (pin "C") (pinfunction "C_C") (pintype "passive"))
      (node (ref "BOOT0") (pin "1") (pinfunction "1_1") (pintype "passive"))
      (node (ref "C10") (pin "1") (pinfunction "1_1") (pintype "passive"))
      (node (ref "C11") (pin "1") (pinfunction "1_1") (pintype "passive"))
      (node (ref "C12") (pin "1") (pinfunction "1_1") (pintype "passive"))
      (node (ref "C13") (pin "1") (pinfunction "1_1") (pintype "passive"))
      (node (ref "C14") (pin "1") (pinfunction "1_1") (pintype "passive"))
      (node (ref "C16") (pin "C") (pinfunction "-_C") (pintype "passive"))
      (node (ref "C17") (pin "1") (pinfunction "1_1") (pintype "passive"))
      (node (ref "C18") (pin "2") (pinfunction "2_2") (pintype "passive"))
      (node (ref "C20") (pin "1") (pinfunction "1_1") (pintype "passive"))
      (node (ref "C29") (pin "2") (pinfunction "2_2") (pintype "passive"))
      (node (ref "C4") (pin "2") (pinfunction "2_2") (pintype "passive"))
      (node (ref "C40") (pin "1") (pinfunction "1_1") (pintype "passive"))
      (node (ref "C41") (pin "1") (pinfunction "1_1") (pintype "passive"))
      (node (ref "C42") (pin "1") (pinfunction "1_1") (pintype "passive"))
      (node (ref "C44") (pin "1") (pinfunction "1_1") (pintype "passive"))
      (node (ref "C45") (pin "1") (pinfunction "1_1") (pintype "passive"))
      (node (ref "C46") (pin "1") (pinfunction "1_1") (pintype "passive"))
      (node (ref "C47") (pin "1") (pinfunction "1_1") (pintype "passive"))
      (node (ref "C48") (pin "1") (pinfunction "1_1") (pintype "passive"))
      (node (ref "C49") (pin "1") (pinfunction "1_1") (pintype "passive"))
      (node (ref "C50") (pin "1") (pinfunction "1_1") (pintype "passive"))
      (node (ref "C51") (pin "1") (pinfunction "1_1") (pintype "passive"))
      (node (ref "C52") (pin "1") (pinfunction "1_1") (pintype "passive"))
      (node (ref "C53") (pin "1") (pinfunction "1_1") (pintype "passive"))
      (node (ref "C54") (pin "1") (pinfunction "1_1") (pintype "passive"))
      (node (ref "C55") (pin "1") (pinfunction "1_1") (pintype "passive"))
      (node (ref "C56") (pin "1") (pinfunction "1_1") (pintype "passive"))
      (node (ref "C57") (pin "1") (pinfunction "1_1") (pintype "passive"))
      (node (ref "C58") (pin "1") (pinfunction "1_1") (pintype "passive"))
      (node (ref "C59") (pin "1") (pinfunction "1_1") (pintype "passive"))
      (node (ref "C8") (pin "1") (pinfunction "1_1") (pintype "passive"))
      (node (ref "C9") (pin "1") (pinfunction "1_1") (pintype "passive"))
      (node (ref "CN2") (pin "3") (pinfunction "3_3") (pintype "passive"))
      (node (ref "CN2") (pin "5") (pinfunction "5_5") (pintype "passive"))
      (node (ref "CN2") (pin "9") (pinfunction "9_9") (pintype "passive"))
      (node (ref "D1") (pin "2") (pinfunction "A_2") (pintype "passive"))
      (node (ref "D13") (pin "C") (pinfunction "C_C") (pintype "passive"))
      (node (ref "D5") (pin "2") (pinfunction "A_2") (pintype "passive"))
      (node (ref "ESP8266-MODULE") (pin "7") (pinfunction "7_7") (pintype "passive"))
      (node (ref "GPS") (pin "GND1") (pinfunction "GND1_GND1") (pintype "bidirectional"))
      (node (ref "GPS") (pin "GND2") (pinfunction "GND2_GND2") (pintype "bidirectional"))
      (node (ref "GPS") (pin "GND3") (pinfunction "GND3_GND3") (pintype "bidirectional"))
      (node (ref "GSM") (pin "GND1") (pinfunction "GND1_GND1") (pintype "bidirectional"))
      (node (ref "GSM") (pin "GND2") (pinfunction "GND2_GND2") (pintype "bidirectional"))
      (node (ref "GSM") (pin "GND3") (pinfunction "GND3_GND3") (pintype "bidirectional"))
      (node (ref "IC1") (pin "2") (pinfunction "VSS_2") (pintype "power_in"))
      (node (ref "IC4") (pin "1") (pinfunction "GND/ADJ_1") (pintype "input"))
      (node (ref "J1") (pin "2") (pinfunction "2_2") (pintype "bidirectional"))
      (node (ref "J11") (pin "3") (pinfunction "P$3_3") (pintype "bidirectional"))
      (node (ref "J2") (pin "9") (pinfunction "9_9") (pintype "bidirectional"))
      (node (ref "J3") (pin "4") (pinfunction "P$4_4") (pintype "bidirectional"))
      (node (ref "J4") (pin "3") (pinfunction "P$3_3") (pintype "bidirectional"))
      (node (ref "J5") (pin "2") (pinfunction "2_2") (pintype "bidirectional"))
      (node (ref "J6") (pin "2") (pinfunction "2_2") (pintype "bidirectional"))
      (node (ref "J7") (pin "10") (pinfunction "G2_10") (pintype "bidirectional"))
      (node (ref "J7") (pin "11") (pinfunction "G3_11") (pintype "bidirectional"))
      (node (ref "J7") (pin "12") (pinfunction "G4_12") (pintype "bidirectional"))
      (node (ref "J7") (pin "6") (pinfunction "VSS_6") (pintype "bidirectional"))
      (node (ref "J7") (pin "9") (pinfunction "G1_9") (pintype "bidirectional"))
      (node (ref "J9") (pin "5") (pinfunction "GND_5") (pintype "power_in"))
      (node (ref "J9") (pin "S1") (pinfunction "SHIELD_S1") (pintype "passive"))
      (node (ref "J9") (pin "S2") (pinfunction "SHIELD_S2") (pintype "passive"))
      (node (ref "J9") (pin "S3") (pinfunction "SHIELD_S3") (pintype "passive"))
      (node (ref "J9") (pin "S4") (pinfunction "SHIELD_S4") (pintype "passive"))
      (node (ref "J9") (pin "S5") (pinfunction "SHIELD_S5") (pintype "passive"))
      (node (ref "J9") (pin "S6") (pinfunction "SHIELD_S6") (pintype "passive"))
      (node (ref "KEY") (pin "1") (pinfunction "1_1") (pintype "passive"))
      (node (ref "NET") (pin "-") (pinfunction "-_-") (pintype "passive"))
      (node (ref "NRST") (pin "1") (pinfunction "1_1") (pintype "passive"))
      (node (ref "Q1") (pin "2") (pinfunction "S_2") (pintype "passive"))
      (node (ref "R13") (pin "2") (pinfunction "2_2") (pintype "passive"))
      (node (ref "R15") (pin "2") (pinfunction "2_2") (pintype "passive"))
      (node (ref "R2") (pin "1") (pinfunction "1_1") (pintype "passive"))
      (node (ref "R8") (pin "1") (pinfunction "1_1") (pintype "passive"))
      (node (ref "STA") (pin "-") (pinfunction "-_-") (pintype "passive"))
      (node (ref "U10") (pin "4") (pinfunction "GND_4") (pintype "power_in"))
      (node (ref "U2") (pin "10") (pinfunction "GND_10") (pintype "bidirectional"))
      (node (ref "U2") (pin "27") (pinfunction "GND_27") (pintype "bidirectional"))
      (node (ref "U2") (pin "29") (pinfunction "GND_29") (pintype "bidirectional"))
      (node (ref "U2") (pin "44") (pinfunction "GND_44") (pintype "bidirectional"))
      (node (ref "U2") (pin "46") (pinfunction "GND_46") (pintype "bidirectional"))
      (node (ref "U2") (pin "55") (pinfunction "GND_55") (pintype "bidirectional"))
      (node (ref "U2") (pin "56") (pinfunction "GND_56") (pintype "bidirectional"))
      (node (ref "U4") (pin "5") (pinfunction "GND_5") (pintype "bidirectional"))
      (node (ref "U5") (pin "4") (pinfunction "GND_4") (pintype "input"))
      (node (ref "U5") (pin "EP") (pinfunction "GND_EP") (pintype "input"))
      (node (ref "U8") (pin "23") (pinfunction "VSS_23") (pintype "power_in"))
      (node (ref "U8") (pin "35") (pinfunction "VSS_35") (pintype "power_in"))
      (node (ref "U8") (pin "47") (pinfunction "VSS_47") (pintype "power_in"))
      (node (ref "U8") (pin "49") (pinfunction "VSS_49") (pintype "power_in"))
      (node (ref "U8") (pin "8") (pinfunction "VSSA_8") (pintype "power_in"))
      (node (ref "U9") (pin "1") (pinfunction "CLKIN_1") (pintype "input"))
      (node (ref "U9") (pin "11") (pinfunction "FSYNC_11") (pintype "input"))
      (node (ref "U9") (pin "18") (pinfunction "GND_18") (pintype "power_in"))
      (node (ref "U9") (pin "9") (pinfunction "AD0_9") (pintype "input"))
      (node (ref "Y3") (pin "2") (pinfunction "GND_2") (pintype "power_in"))
      (node (ref "Y3") (pin "4") (pinfunction "GND_4") (pintype "power_in"))
    )
    (net (code "63") (name "Net-(+3V3-PWR-Pad+)") (class "Default")
      (node (ref "+3V3-PWR") (pin "+") (pinfunction "+_+") (pintype "passive"))
      (node (ref "R7") (pin "2") (pinfunction "2_2") (pintype "passive"))
    )
    (net (code "64") (name "Net-(+5V5-PWR-PadA)") (class "Default")
      (node (ref "+5V5-PWR") (pin "A") (pinfunction "A_A") (pintype "passive"))
      (node (ref "R1") (pin "1") (pinfunction "1_1") (pintype "passive"))
    )
    (net (code "65") (name "Net-(C13-Pad2)") (class "Default")
      (node (ref "C13") (pin "2") (pinfunction "2_2") (pintype "passive"))
      (node (ref "GSM") (pin "D") (pinfunction "D_D") (pintype "bidirectional"))
      (node (ref "R6") (pin "2") (pinfunction "2_2") (pintype "passive"))
    )
    (net (code "66") (name "Net-(CHG-Pad-)") (class "Default")
      (node (ref "CHG") (pin "-") (pinfunction "-_-") (pintype "passive"))
      (node (ref "R12") (pin "1") (pinfunction "1_1") (pintype "passive"))
    )
    (net (code "67") (name "Net-(D2-PadC)") (class "Default")
      (node (ref "D2") (pin "C") (pinfunction "C_C") (pintype "passive"))
      (node (ref "D3") (pin "A") (pinfunction "A_A") (pintype "passive"))
    )
    (net (code "68") (name "Net-(D13-PadA)") (class "Default")
      (node (ref "D13") (pin "A") (pinfunction "A_A") (pintype "passive"))
      (node (ref "R19") (pin "1") (pinfunction "1_1") (pintype "passive"))
    )
    (net (code "69") (name "Net-(IC1-PROG)") (class "Default")
      (node (ref "IC1") (pin "5") (pinfunction "PROG_5") (pintype "input"))
      (node (ref "R13") (pin "1") (pinfunction "1_1") (pintype "passive"))
    )
    (net (code "70") (name "Net-(IC1-STAT)") (class "Default")
      (node (ref "IC1") (pin "1") (pinfunction "STAT_1") (pintype "output"))
      (node (ref "R12") (pin "2") (pinfunction "2_2") (pintype "passive"))
    )
    (net (code "71") (name "Net-(IC4-IN)") (class "Default")
      (node (ref "C20") (pin "2") (pinfunction "2_2") (pintype "passive"))
      (node (ref "IC4") (pin "3") (pinfunction "IN_3") (pintype "input"))
      (node (ref "RT1") (pin "1") (pinfunction "1_1") (pintype "passive"))
    )
    (net (code "72") (name "Net-(J5-Pad1)") (class "Default")
      (node (ref "J5") (pin "1") (pinfunction "1_1") (pintype "bidirectional"))
      (node (ref "RT1") (pin "2") (pinfunction "2_2") (pintype "passive"))
    )
    (net (code "73") (name "Net-(NET-Pad+)") (class "Default")
      (node (ref "NET") (pin "+") (pinfunction "+_+") (pintype "passive"))
      (node (ref "R3") (pin "2") (pinfunction "2_2") (pintype "passive"))
    )
    (net (code "74") (name "Net-(Q1-D)") (class "Default")
      (node (ref "Q1") (pin "3") (pinfunction "D_3") (pintype "passive"))
      (node (ref "U2") (pin "18") (pinfunction "RESET_18") (pintype "bidirectional"))
    )
    (net (code "75") (name "Net-(R4-Pad2)") (class "Default")
      (node (ref "R4") (pin "2") (pinfunction "2_2") (pintype "passive"))
      (node (ref "STA") (pin "+") (pinfunction "+_+") (pintype "passive"))
    )
    (net (code "76") (name "PC13") (class "Default")
      (node (ref "R19") (pin "2") (pinfunction "2_2") (pintype "passive"))
    )
    (net (code "77") (name "VBUS") (class "Default")
      (node (ref "C41") (pin "2") (pinfunction "2_2") (pintype "passive"))
      (node (ref "D6") (pin "1") (pinfunction "A1_1") (pintype "passive"))
      (node (ref "FL3") (pin "2") (pinfunction "2_2") (pintype "passive"))
    )
    (net (code "78") (name "VCC") (class "Default")
      (node (ref "C9") (pin "2") (pinfunction "2_2") (pintype "passive"))
      (node (ref "CHG") (pin "+") (pinfunction "+_+") (pintype "passive"))
      (node (ref "D6") (pin "3") (pinfunction "C_3") (pintype "passive"))
      (node (ref "IC1") (pin "4") (pinfunction "VDD_4") (pintype "power_in"))
      (node (ref "J1") (pin "1") (pinfunction "1_1") (pintype "bidirectional"))
      (node (ref "J2") (pin "10") (pinfunction "10_10") (pintype "bidirectional"))
      (node (ref "SW1") (pin "COM2") (pinfunction "COM2_COM2") (pintype "bidirectional"))
    )
    (net (code "79") (name "unconnected-(CN2-Pad7)") (class "Default")
      (node (ref "CN2") (pin "7") (pinfunction "7_7") (pintype "passive"))
    )
    (net (code "80") (name "unconnected-(CN2-Pad8)") (class "Default")
      (node (ref "CN2") (pin "8") (pinfunction "8_8") (pintype "passive"))
    )
    (net (code "81") (name "unconnected-(D5-C5-Pad6)") (class "Default")
      (node (ref "D5") (pin "6") (pinfunction "C5_6") (pintype "passive"))
    )
    (net (code "82") (name "unconnected-(ESP8266-MODULE-Pad3)") (class "Default")
      (node (ref "ESP8266-MODULE") (pin "3") (pinfunction "3_3") (pintype "passive"))
    )
    (net (code "83") (name "unconnected-(ESP8266-MODULE-Pad5)") (class "Default")
      (node (ref "ESP8266-MODULE") (pin "5") (pinfunction "5_5") (pintype "passive"))
    )
    (net (code "84") (name "unconnected-(ESP8266-MODULE-Pad6)") (class "Default")
      (node (ref "ESP8266-MODULE") (pin "6") (pinfunction "6_6") (pintype "passive"))
    )
    (net (code "85") (name "unconnected-(J7-RSV{slash}D1-Pad8)") (class "Default")
      (node (ref "J7") (pin "8") (pinfunction "RSV/D1_8") (pintype "bidirectional"))
    )
    (net (code "86") (name "unconnected-(J7-RSV{slash}D2-Pad1)") (class "Default")
      (node (ref "J7") (pin "1") (pinfunction "RSV/D2_1") (pintype "bidirectional"))
    )
    (net (code "87") (name "unconnected-(J9-ID-Pad4)") (class "Default")
      (node (ref "J9") (pin "4") (pinfunction "ID_4") (pintype "bidirectional"))
    )
    (net (code "88") (name "unconnected-(SW1-PadCH1B)") (class "Default")
      (node (ref "SW1") (pin "CH1B") (pinfunction "CH1B_CH1B") (pintype "bidirectional"))
    )
    (net (code "89") (name "unconnected-(SW1-PadCH2B)") (class "Default")
      (node (ref "SW1") (pin "CH2B") (pinfunction "CH2B_CH2B") (pintype "bidirectional"))
    )
    (net (code "90") (name "unconnected-(U2-ADC0-Pad15)") (class "Default")
      (node (ref "U2") (pin "15") (pinfunction "ADC0_15") (pintype "bidirectional"))
    )
    (net (code "91") (name "unconnected-(U2-ADC1-Pad16)") (class "Default")
      (node (ref "U2") (pin "16") (pinfunction "ADC1_16") (pintype "bidirectional"))
    )
    (net (code "92") (name "unconnected-(U2-I2C2_SCL-Pad1)") (class "Default")
      (node (ref "U2") (pin "1") (pinfunction "I2C2_SCL_1") (pintype "bidirectional"))
    )
    (net (code "93") (name "unconnected-(U2-I2C2_SDA-Pad2)") (class "Default")
      (node (ref "U2") (pin "2") (pinfunction "I2C2_SDA_2") (pintype "bidirectional"))
    )
    (net (code "94") (name "unconnected-(U2-IO26-Pad25)") (class "Default")
      (node (ref "U2") (pin "25") (pinfunction "IO26_25") (pintype "bidirectional"))
    )
    (net (code "95") (name "unconnected-(U2-IO29-Pad24)") (class "Default")
      (node (ref "U2") (pin "24") (pinfunction "IO29_24") (pintype "bidirectional"))
    )
    (net (code "96") (name "unconnected-(U2-IO30-Pad31)") (class "Default")
      (node (ref "U2") (pin "31") (pinfunction "IO30_31") (pintype "bidirectional"))
    )
    (net (code "97") (name "unconnected-(U2-LCD_CS-Pad19)") (class "Default")
      (node (ref "U2") (pin "19") (pinfunction "LCD_CS_19") (pintype "bidirectional"))
    )
    (net (code "98") (name "unconnected-(U2-LCD_DIO-Pad21)") (class "Default")
      (node (ref "U2") (pin "21") (pinfunction "LCD_DIO_21") (pintype "bidirectional"))
    )
    (net (code "99") (name "unconnected-(U2-LCD_RST-Pad20)") (class "Default")
      (node (ref "U2") (pin "20") (pinfunction "LCD_RST_20") (pintype "bidirectional"))
    )
    (net (code "100") (name "unconnected-(U2-LCD_SCK-Pad23)") (class "Default")
      (node (ref "U2") (pin "23") (pinfunction "LCD_SCK_23") (pintype "bidirectional"))
    )
    (net (code "101") (name "unconnected-(U2-LCD_SDC-Pad22)") (class "Default")
      (node (ref "U2") (pin "22") (pinfunction "LCD_SDC_22") (pintype "bidirectional"))
    )
    (net (code "102") (name "unconnected-(U2-MIC_N-Pad33)") (class "Default")
      (node (ref "U2") (pin "33") (pinfunction "MIC_N_33") (pintype "bidirectional"))
    )
    (net (code "103") (name "unconnected-(U2-MIC_P-Pad34)") (class "Default")
      (node (ref "U2") (pin "34") (pinfunction "MIC_P_34") (pintype "bidirectional"))
    )
    (net (code "104") (name "unconnected-(U2-SD_CLK-Pad8)") (class "Default")
      (node (ref "U2") (pin "8") (pinfunction "SD_CLK_8") (pintype "bidirectional"))
    )
    (net (code "105") (name "unconnected-(U2-SD_CMD-Pad7)") (class "Default")
      (node (ref "U2") (pin "7") (pinfunction "SD_CMD_7") (pintype "bidirectional"))
    )
    (net (code "106") (name "unconnected-(U2-SD_D0-Pad6)") (class "Default")
      (node (ref "U2") (pin "6") (pinfunction "SD_D0_6") (pintype "bidirectional"))
    )
    (net (code "107") (name "unconnected-(U2-SD_D1-Pad5)") (class "Default")
      (node (ref "U2") (pin "5") (pinfunction "SD_D1_5") (pintype "bidirectional"))
    )
    (net (code "108") (name "unconnected-(U2-SD_D2-Pad4)") (class "Default")
      (node (ref "U2") (pin "4") (pinfunction "SD_D2_4") (pintype "bidirectional"))
    )
    (net (code "109") (name "unconnected-(U2-SD_D3-Pad3)") (class "Default")
      (node (ref "U2") (pin "3") (pinfunction "SD_D3_3") (pintype "bidirectional"))
    )
    (net (code "110") (name "unconnected-(U2-SPK_N-Pad14)") (class "Default")
      (node (ref "U2") (pin "14") (pinfunction "SPK_N_14") (pintype "bidirectional"))
    )
    (net (code "111") (name "unconnected-(U2-SPK_P-Pad13)") (class "Default")
      (node (ref "U2") (pin "13") (pinfunction "SPK_P_13") (pintype "bidirectional"))
    )
    (net (code "112") (name "unconnected-(U2-UART1_CTS-Pad52)") (class "Default")
      (node (ref "U2") (pin "52") (pinfunction "UART1_CTS_52") (pintype "bidirectional"))
    )
    (net (code "113") (name "unconnected-(U2-UART1_RTS-Pad51)") (class "Default")
      (node (ref "U2") (pin "51") (pinfunction "UART1_RTS_51") (pintype "bidirectional"))
    )
    (net (code "114") (name "unconnected-(U2-UART2_CTS-Pad48)") (class "Default")
      (node (ref "U2") (pin "48") (pinfunction "UART2_CTS_48") (pintype "bidirectional"))
    )
    (net (code "115") (name "unconnected-(U2-UART2_RTS-Pad47)") (class "Default")
      (node (ref "U2") (pin "47") (pinfunction "UART2_RTS_47") (pintype "bidirectional"))
    )
    (net (code "116") (name "unconnected-(U2-UART2_RXD-Pad49)") (class "Default")
      (node (ref "U2") (pin "49") (pinfunction "UART2_RXD_49") (pintype "bidirectional"))
    )
    (net (code "117") (name "unconnected-(U2-UART2_TXD-Pad50)") (class "Default")
      (node (ref "U2") (pin "50") (pinfunction "UART2_TXD_50") (pintype "bidirectional"))
    )
    (net (code "118") (name "unconnected-(U2-USB_N-Pad35)") (class "Default")
      (node (ref "U2") (pin "35") (pinfunction "USB_N_35") (pintype "bidirectional"))
    )
    (net (code "119") (name "unconnected-(U2-USB_P-Pad36)") (class "Default")
      (node (ref "U2") (pin "36") (pinfunction "USB_P_36") (pintype "bidirectional"))
    )
    (net (code "120") (name "unconnected-(U2-VUSB-Pad17)") (class "Default")
      (node (ref "U2") (pin "17") (pinfunction "VUSB_17") (pintype "bidirectional"))
    )
    (net (code "121") (name "unconnected-(U4-VPP-Pad6)") (class "Default")
      (node (ref "U4") (pin "6") (pinfunction "VPP_6") (pintype "bidirectional"))
    )
    (net (code "122") (name "unconnected-(U9-AUX_CL-Pad7)") (class "Default")
      (node (ref "U9") (pin "7") (pinfunction "AUX_CL_7") (pintype "input"))
    )
    (net (code "123") (name "unconnected-(U9-AUX_DA-Pad6)") (class "Default")
      (node (ref "U9") (pin "6") (pinfunction "AUX_DA_6") (pintype "bidirectional"))
    )
    (net (code "124") (name "unconnected-(U9-RESV-Pad19)") (class "Default")
      (node (ref "U9") (pin "19") (pinfunction "RESV_19") (pintype "passive"))
    )
    (net (code "125") (name "unconnected-(U9-RESV-Pad21)") (class "Default")
      (node (ref "U9") (pin "21") (pinfunction "RESV_21") (pintype "passive"))
    )
    (net (code "126") (name "unconnected-(U9-RESV-Pad22)") (class "Default")
      (node (ref "U9") (pin "22") (pinfunction "RESV_22") (pintype "passive"))
    )
  )
)
